# Jasmine.net
KiCad netlist of a schematic drawn in EAGLE
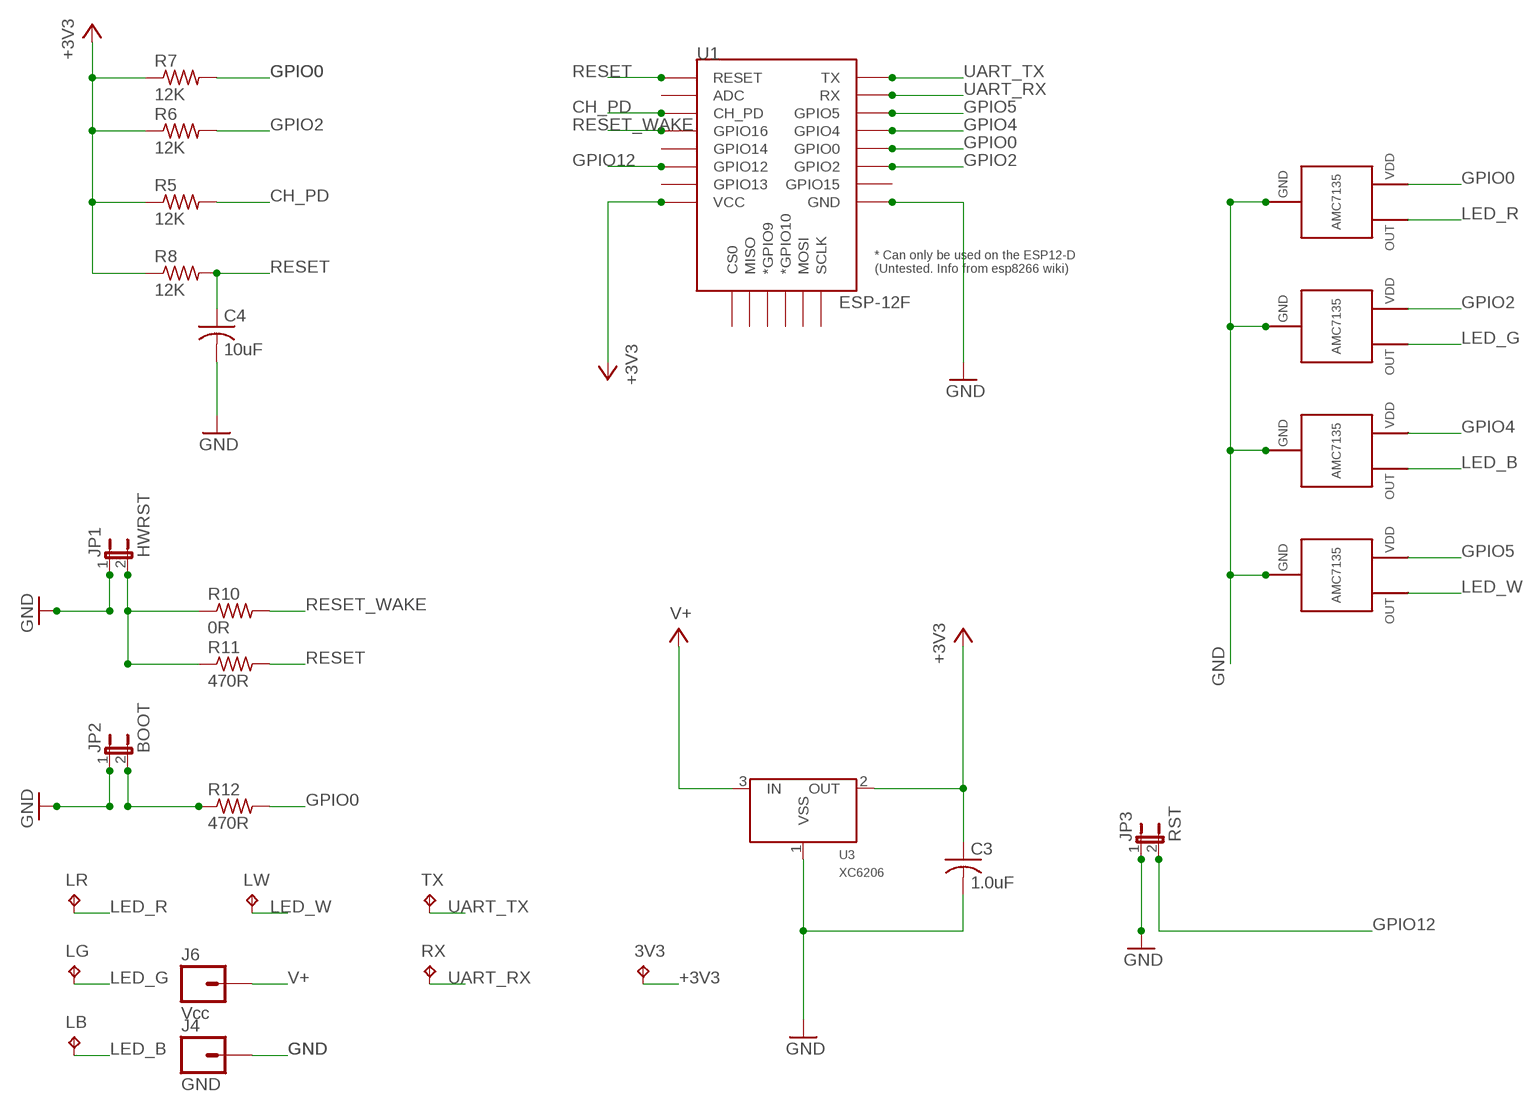
[diagram p0: schematic, sheet 1]

(export (version "E")
  (design (tool "Eeschema 10.0.6"))
  (components
    (comp (ref "3V3")
      (value "TPB2,54")
      (footprint "eagle-import:B2,54")
      (libsource (lib "eagle-import") (part "TPB2,54"))
    )
    (comp (ref "C3")
      (value "1.0uF")
      (footprint "eagle-import:C0805K")
      (libsource (lib "eagle-import") (part "C-USC0805K"))
    )
    (comp (ref "C4")
      (value "10uF")
      (footprint "eagle-import:C0805")
      (libsource (lib "eagle-import") (part "C-USC0805"))
    )
    (comp (ref "J4")
      (value "GND")
      (footprint "eagle-import:1X01_2MM")
      (libsource (lib "eagle-import") (part "M01PTH_2MM"))
    )
    (comp (ref "J6")
      (value "Vcc")
      (footprint "eagle-import:1X01_2MM")
      (libsource (lib "eagle-import") (part "M01PTH_2MM"))
    )
    (comp (ref "JP1")
      (value "HWRST")
      (footprint "eagle-import:SJ_2S-NO")
      (libsource (lib "eagle-import") (part "JUMPER-2SMD-NO"))
    )
    (comp (ref "JP2")
      (value "BOOT")
      (footprint "eagle-import:SJ_2S-NO")
      (libsource (lib "eagle-import") (part "JUMPER-2SMD-NO"))
    )
    (comp (ref "JP3")
      (value "RST")
      (footprint "eagle-import:SJ_2S-NO")
      (libsource (lib "eagle-import") (part "JUMPER-2SMD-NO"))
    )
    (comp (ref "LB")
      (value "TPB2,54")
      (footprint "eagle-import:B2,54")
      (libsource (lib "eagle-import") (part "TPB2,54"))
    )
    (comp (ref "LG")
      (value "TPB2,54")
      (footprint "eagle-import:B2,54")
      (libsource (lib "eagle-import") (part "TPB2,54"))
    )
    (comp (ref "LR")
      (value "TPB2,54")
      (footprint "eagle-import:B2,54")
      (libsource (lib "eagle-import") (part "TPB2,54"))
    )
    (comp (ref "LW")
      (value "TPB2,54")
      (footprint "eagle-import:B2,54")
      (libsource (lib "eagle-import") (part "TPB2,54"))
    )
    (comp (ref "R5")
      (value "12K")
      (footprint "eagle-import:R0805")
      (libsource (lib "eagle-import") (part "R-US_R0805"))
    )
    (comp (ref "R6")
      (value "12K")
      (footprint "eagle-import:R0805")
      (libsource (lib "eagle-import") (part "R-US_R0805"))
    )
    (comp (ref "R7")
      (value "12K")
      (footprint "eagle-import:R0805")
      (libsource (lib "eagle-import") (part "R-US_R0805"))
    )
    (comp (ref "R8")
      (value "12K")
      (footprint "eagle-import:R0805")
      (libsource (lib "eagle-import") (part "R-US_R0805"))
    )
    (comp (ref "R10")
      (value "0R")
      (footprint "eagle-import:R0805")
      (libsource (lib "eagle-import") (part "R-US_R0805"))
    )
    (comp (ref "R11")
      (value "470R")
      (footprint "eagle-import:R0805")
      (libsource (lib "eagle-import") (part "R-US_R0805"))
    )
    (comp (ref "R12")
      (value "470R")
      (footprint "eagle-import:R0805")
      (libsource (lib "eagle-import") (part "R-US_R0805"))
    )
    (comp (ref "RX")
      (value "TPB2,54")
      (footprint "eagle-import:B2,54")
      (libsource (lib "eagle-import") (part "TPB2,54"))
    )
    (comp (ref "TX")
      (value "TPB2,54")
      (footprint "eagle-import:B2,54")
      (libsource (lib "eagle-import") (part "TPB2,54"))
    )
    (comp (ref "U$1")
      (value "AMC7135_CC_REGULATOR")
      (footprint "eagle-import:AMC7135_CC_REGULATOR")
      (libsource (lib "eagle-import") (part "AMC7135_CC_REGULATOR"))
    )
    (comp (ref "U$2")
      (value "AMC7135_CC_REGULATOR")
      (footprint "eagle-import:AMC7135_CC_REGULATOR")
      (libsource (lib "eagle-import") (part "AMC7135_CC_REGULATOR"))
    )
    (comp (ref "U$3")
      (value "AMC7135_CC_REGULATOR")
      (footprint "eagle-import:AMC7135_CC_REGULATOR")
      (libsource (lib "eagle-import") (part "AMC7135_CC_REGULATOR"))
    )
    (comp (ref "U$4")
      (value "AMC7135_CC_REGULATOR")
      (footprint "eagle-import:AMC7135_CC_REGULATOR")
      (libsource (lib "eagle-import") (part "AMC7135_CC_REGULATOR"))
    )
    (comp (ref "U1")
      (value "ESP-12F")
      (footprint "eagle-import:ESP12E-SMD")
      (libsource (lib "eagle-import") (part "ESP12ESMD"))
    )
    (comp (ref "U3")
      (value "XC6206")
      (footprint "eagle-import:XC6206_SOT-23")
      (libsource (lib "eagle-import") (part "XC6206SOT-23"))
    )
  )
  (nets
    (net (code "1") (name "+3V3") (class "Default")
      (node (ref "3V3") (pin "TP") (pinfunction "TP_TP") (pintype "input"))
      (node (ref "C3") (pin "1") (pinfunction "1_1") (pintype "passive"))
      (node (ref "R5") (pin "1") (pinfunction "1_1") (pintype "passive"))
      (node (ref "R6") (pin "1") (pinfunction "1_1") (pintype "passive"))
      (node (ref "R7") (pin "1") (pinfunction "1_1") (pintype "passive"))
      (node (ref "R8") (pin "1") (pinfunction "1_1") (pintype "passive"))
      (node (ref "U1") (pin "VCC") (pinfunction "VCC_VCC") (pintype "bidirectional"))
      (node (ref "U3") (pin "2") (pinfunction "OUT_2") (pintype "bidirectional"))
    )
    (net (code "2") (name "/CH_PD") (class "Default")
      (node (ref "R5") (pin "2") (pinfunction "2_2") (pintype "passive"))
      (node (ref "U1") (pin "CH_PD") (pinfunction "CH_PD_CH_PD") (pintype "bidirectional"))
    )
    (net (code "3") (name "/GPIO0") (class "Default")
      (node (ref "R12") (pin "2") (pinfunction "2_2") (pintype "passive"))
      (node (ref "R7") (pin "2") (pinfunction "2_2") (pintype "passive"))
      (node (ref "U$2") (pin "VDD") (pinfunction "VDD_VDD") (pintype "bidirectional"))
      (node (ref "U1") (pin "GPIO0") (pinfunction "GPIO0_GPIO0") (pintype "bidirectional"))
    )
    (net (code "4") (name "/GPIO2") (class "Default")
      (node (ref "R6") (pin "2") (pinfunction "2_2") (pintype "passive"))
      (node (ref "U$1") (pin "VDD") (pinfunction "VDD_VDD") (pintype "bidirectional"))
      (node (ref "U1") (pin "GPIO2") (pinfunction "GPIO2_GPIO2") (pintype "bidirectional"))
    )
    (net (code "5") (name "/GPIO4") (class "Default")
      (node (ref "U$3") (pin "VDD") (pinfunction "VDD_VDD") (pintype "bidirectional"))
      (node (ref "U1") (pin "GPIO4") (pinfunction "GPIO4_GPIO4") (pintype "bidirectional"))
    )
    (net (code "6") (name "/GPIO5") (class "Default")
      (node (ref "U$4") (pin "VDD") (pinfunction "VDD_VDD") (pintype "bidirectional"))
      (node (ref "U1") (pin "GPIO5") (pinfunction "GPIO5_GPIO5") (pintype "bidirectional"))
    )
    (net (code "7") (name "/GPIO12") (class "Default")
      (node (ref "JP3") (pin "2") (pinfunction "2_2") (pintype "passive"))
      (node (ref "U1") (pin "GPIO12") (pinfunction "GPIO12_GPIO12") (pintype "bidirectional"))
    )
    (net (code "8") (name "/LED_B") (class "Default")
      (node (ref "LB") (pin "TP") (pinfunction "TP_TP") (pintype "input"))
      (node (ref "U$3") (pin "OUT") (pinfunction "OUT_OUT") (pintype "bidirectional"))
    )
    (net (code "9") (name "/LED_G") (class "Default")
      (node (ref "LG") (pin "TP") (pinfunction "TP_TP") (pintype "input"))
      (node (ref "U$1") (pin "OUT") (pinfunction "OUT_OUT") (pintype "bidirectional"))
    )
    (net (code "10") (name "/LED_R") (class "Default")
      (node (ref "LR") (pin "TP") (pinfunction "TP_TP") (pintype "input"))
      (node (ref "U$2") (pin "OUT") (pinfunction "OUT_OUT") (pintype "bidirectional"))
    )
    (net (code "11") (name "/LED_W") (class "Default")
      (node (ref "LW") (pin "TP") (pinfunction "TP_TP") (pintype "input"))
      (node (ref "U$4") (pin "OUT") (pinfunction "OUT_OUT") (pintype "bidirectional"))
    )
    (net (code "12") (name "/RESET") (class "Default")
      (node (ref "C4") (pin "1") (pinfunction "1_1") (pintype "passive"))
      (node (ref "R11") (pin "2") (pinfunction "2_2") (pintype "passive"))
      (node (ref "R8") (pin "2") (pinfunction "2_2") (pintype "passive"))
      (node (ref "U1") (pin "RESET") (pinfunction "RESET_RESET") (pintype "bidirectional"))
    )
    (net (code "13") (name "/RESET_WAKE") (class "Default")
      (node (ref "R10") (pin "2") (pinfunction "2_2") (pintype "passive"))
      (node (ref "U1") (pin "GPIO16") (pinfunction "GPIO16_GPIO16") (pintype "bidirectional"))
    )
    (net (code "14") (name "/UART_RX") (class "Default")
      (node (ref "RX") (pin "TP") (pinfunction "TP_TP") (pintype "input"))
      (node (ref "U1") (pin "RXD0") (pinfunction "RX_RXD0") (pintype "bidirectional"))
    )
    (net (code "15") (name "/UART_TX") (class "Default")
      (node (ref "TX") (pin "TP") (pinfunction "TP_TP") (pintype "input"))
      (node (ref "U1") (pin "TXD0") (pinfunction "TX_TXD0") (pintype "bidirectional"))
    )
    (net (code "16") (name "GND") (class "Default")
      (node (ref "C3") (pin "2") (pinfunction "2_2") (pintype "passive"))
      (node (ref "C4") (pin "2") (pinfunction "2_2") (pintype "passive"))
      (node (ref "J4") (pin "1") (pinfunction "1_1") (pintype "passive"))
      (node (ref "JP1") (pin "1") (pinfunction "1_1") (pintype "passive"))
      (node (ref "JP2") (pin "1") (pinfunction "1_1") (pintype "passive"))
      (node (ref "JP3") (pin "1") (pinfunction "1_1") (pintype "passive"))
      (node (ref "U$1") (pin "GND2") (pinfunction "GND_GND2") (pintype "bidirectional"))
      (node (ref "U$1") (pin "GND3") (pinfunction "GND_GND3") (pintype "bidirectional"))
      (node (ref "U$2") (pin "GND2") (pinfunction "GND_GND2") (pintype "bidirectional"))
      (node (ref "U$2") (pin "GND3") (pinfunction "GND_GND3") (pintype "bidirectional"))
      (node (ref "U$3") (pin "GND2") (pinfunction "GND_GND2") (pintype "bidirectional"))
      (node (ref "U$3") (pin "GND3") (pinfunction "GND_GND3") (pintype "bidirectional"))
      (node (ref "U$4") (pin "GND2") (pinfunction "GND_GND2") (pintype "bidirectional"))
      (node (ref "U$4") (pin "GND3") (pinfunction "GND_GND3") (pintype "bidirectional"))
      (node (ref "U1") (pin "GND") (pinfunction "GND_GND") (pintype "bidirectional"))
      (node (ref "U3") (pin "1") (pinfunction "VSS_1") (pintype "bidirectional"))
    )
    (net (code "17") (name "Net-(JP1-Pad2)") (class "Default")
      (node (ref "JP1") (pin "2") (pinfunction "2_2") (pintype "passive"))
      (node (ref "R10") (pin "1") (pinfunction "1_1") (pintype "passive"))
      (node (ref "R11") (pin "1") (pinfunction "1_1") (pintype "passive"))
    )
    (net (code "18") (name "Net-(JP2-Pad2)") (class "Default")
      (node (ref "JP2") (pin "2") (pinfunction "2_2") (pintype "passive"))
      (node (ref "R12") (pin "1") (pinfunction "1_1") (pintype "passive"))
    )
    (net (code "19") (name "V+") (class "Default")
      (node (ref "J6") (pin "1") (pinfunction "1_1") (pintype "passive"))
      (node (ref "U3") (pin "3") (pinfunction "IN_3") (pintype "bidirectional"))
    )
    (net (code "20") (name "unconnected-(U1-*GPIO9-PadGPIO9)") (class "Default")
      (node (ref "U1") (pin "GPIO9") (pinfunction "*GPIO9_GPIO9") (pintype "bidirectional"))
    )
    (net (code "21") (name "unconnected-(U1-*GPIO10-PadGPIO10)") (class "Default")
      (node (ref "U1") (pin "GPIO10") (pinfunction "*GPIO10_GPIO10") (pintype "bidirectional"))
    )
    (net (code "22") (name "unconnected-(U1-PadADC)") (class "Default")
      (node (ref "U1") (pin "ADC") (pinfunction "ADC_ADC") (pintype "bidirectional"))
    )
    (net (code "23") (name "unconnected-(U1-PadCS0)") (class "Default")
      (node (ref "U1") (pin "CS0") (pinfunction "CS0_CS0") (pintype "bidirectional"))
    )
    (net (code "24") (name "unconnected-(U1-PadGPIO13)") (class "Default")
      (node (ref "U1") (pin "GPIO13") (pinfunction "GPIO13_GPIO13") (pintype "bidirectional"))
    )
    (net (code "25") (name "unconnected-(U1-PadGPIO14)") (class "Default")
      (node (ref "U1") (pin "GPIO14") (pinfunction "GPIO14_GPIO14") (pintype "bidirectional"))
    )
    (net (code "26") (name "unconnected-(U1-PadGPIO15)") (class "Default")
      (node (ref "U1") (pin "GPIO15") (pinfunction "GPIO15_GPIO15") (pintype "bidirectional"))
    )
    (net (code "27") (name "unconnected-(U1-PadMISO)") (class "Default")
      (node (ref "U1") (pin "MISO") (pinfunction "MISO_MISO") (pintype "bidirectional"))
    )
    (net (code "28") (name "unconnected-(U1-PadMOSI)") (class "Default")
      (node (ref "U1") (pin "MOSI") (pinfunction "MOSI_MOSI") (pintype "bidirectional"))
    )
    (net (code "29") (name "unconnected-(U1-PadSCLK)") (class "Default")
      (node (ref "U1") (pin "SCLK") (pinfunction "SCLK_SCLK") (pintype "bidirectional"))
    )
  )
)
